# stm_board_f407_1_2_3.net
KiCad netlist of a schematic drawn in EAGLE
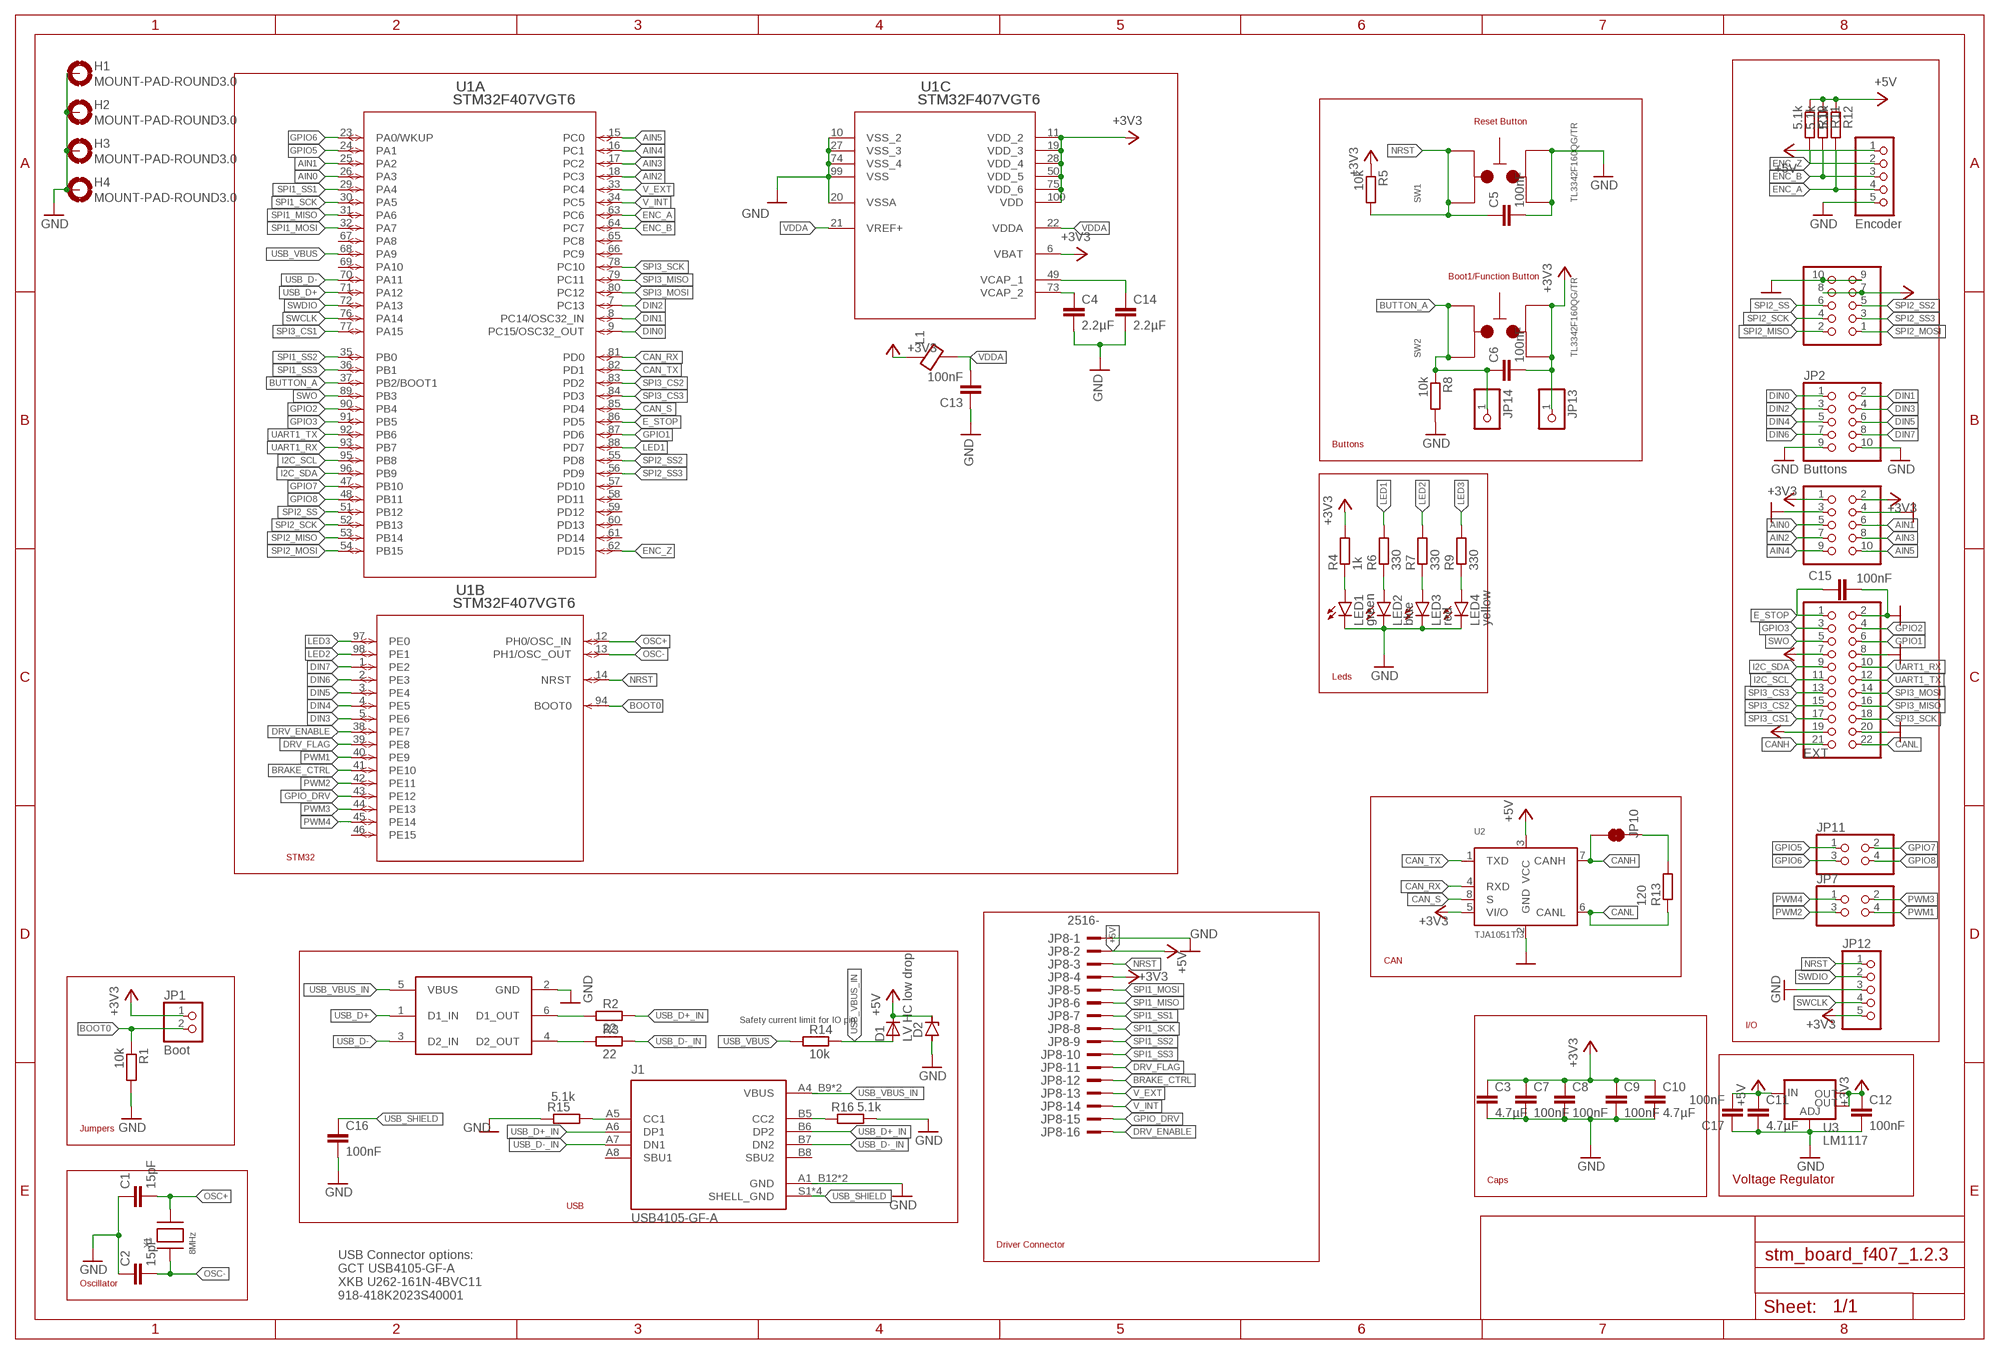
[diagram p0: schematic, sheet 1]

(export (version "E")
  (design (tool "Eeschema 10.0.6"))
  (components
    (comp (ref "C1")
      (value "15pF")
      (footprint "eagle-import:C0603")
      (libsource (lib "eagle-import") (part "C-EUC0603"))
    )
    (comp (ref "C2")
      (value "15pF")
      (footprint "eagle-import:C0603")
      (libsource (lib "eagle-import") (part "C-EUC0603"))
    )
    (comp (ref "C3")
      (value "4.7µF")
      (footprint "eagle-import:C0805")
      (libsource (lib "eagle-import") (part "C-EUC0805"))
    )
    (comp (ref "C4")
      (value "2.2µF")
      (footprint "eagle-import:C0603")
      (libsource (lib "eagle-import") (part "C-EUC0603"))
    )
    (comp (ref "C5")
      (value "100nF")
      (footprint "eagle-import:C0603")
      (libsource (lib "eagle-import") (part "C-EUC0603"))
    )
    (comp (ref "C6")
      (value "100nF")
      (footprint "eagle-import:C0603")
      (libsource (lib "eagle-import") (part "C-EUC0603"))
    )
    (comp (ref "C7")
      (value "100nF")
      (footprint "eagle-import:C0603")
      (libsource (lib "eagle-import") (part "C-EUC0603"))
    )
    (comp (ref "C8")
      (value "100nF")
      (footprint "eagle-import:C0603")
      (libsource (lib "eagle-import") (part "C-EUC0603"))
    )
    (comp (ref "C9")
      (value "100nF")
      (footprint "eagle-import:C0603")
      (libsource (lib "eagle-import") (part "C-EUC0603"))
    )
    (comp (ref "C10")
      (value "4.7µF")
      (footprint "eagle-import:C0805")
      (libsource (lib "eagle-import") (part "C-EUC0805"))
    )
    (comp (ref "C11")
      (value "4.7µF")
      (footprint "eagle-import:C0805")
      (libsource (lib "eagle-import") (part "C-EUC0805"))
    )
    (comp (ref "C12")
      (value "100nF")
      (footprint "eagle-import:C0603")
      (libsource (lib "eagle-import") (part "C-EUC0603"))
    )
    (comp (ref "C13")
      (value "100nF")
      (footprint "eagle-import:C0603")
      (libsource (lib "eagle-import") (part "C-EUC0603"))
    )
    (comp (ref "C14")
      (value "2.2µF")
      (footprint "eagle-import:C0603")
      (libsource (lib "eagle-import") (part "C-EUC0603"))
    )
    (comp (ref "C15")
      (value "100nF")
      (footprint "eagle-import:C0603")
      (libsource (lib "eagle-import") (part "C-EUC0603"))
    )
    (comp (ref "C16")
      (value "100nF")
      (footprint "eagle-import:C0603")
      (libsource (lib "eagle-import") (part "C-EUC0603"))
    )
    (comp (ref "C17")
      (value "100nF")
      (footprint "eagle-import:C0603")
      (libsource (lib "eagle-import") (part "C-EUC0603"))
    )
    (comp (ref "D1")
      (value "LV HC low drop")
      (footprint "eagle-import:SMADIODE")
      (libsource (lib "eagle-import") (part "DIODESMA"))
    )
    (comp (ref "D2")
      (value "ZENER-DIODESOD80C")
      (footprint "eagle-import:SOD80C")
      (libsource (lib "eagle-import") (part "ZENER-DIODESOD80C"))
    )
    (comp (ref "H1")
      (value "MOUNT-PAD-ROUND3.0")
      (footprint "eagle-import:3,0-PAD")
      (libsource (lib "eagle-import") (part "MOUNT-PAD-ROUND3.0"))
    )
    (comp (ref "H2")
      (value "MOUNT-PAD-ROUND3.0")
      (footprint "eagle-import:3,0-PAD")
      (libsource (lib "eagle-import") (part "MOUNT-PAD-ROUND3.0"))
    )
    (comp (ref "H3")
      (value "MOUNT-PAD-ROUND3.0")
      (footprint "eagle-import:3,0-PAD")
      (libsource (lib "eagle-import") (part "MOUNT-PAD-ROUND3.0"))
    )
    (comp (ref "H4")
      (value "MOUNT-PAD-ROUND3.0")
      (footprint "eagle-import:3,0-PAD")
      (libsource (lib "eagle-import") (part "MOUNT-PAD-ROUND3.0"))
    )
    (comp (ref "J1")
      (value "USB4105-GF-A")
      (footprint "eagle-import:GCT_USB4105-GF-A")
      (fields (field (name "MF") "GCT"))
      (libsource (lib "eagle-import") (part "USB4105-GF-A"))
    )
    (comp (ref "JP1")
      (value "Boot")
      (footprint "eagle-import:1X02")
      (libsource (lib "eagle-import") (part "PINHD-1X2"))
    )
    (comp (ref "JP2")
      (value "Buttons")
      (footprint "eagle-import:2X05")
      (libsource (lib "eagle-import") (part "PINHD-2X5"))
    )
    (comp (ref "JP3")
      (value "Analog")
      (footprint "eagle-import:2X05")
      (libsource (lib "eagle-import") (part "PINHD-2X5"))
    )
    (comp (ref "JP4")
      (value "EXT")
      (footprint "eagle-import:2X11")
      (libsource (lib "eagle-import") (part "PINHD-2X11"))
    )
    (comp (ref "JP5")
      (value "Encoder")
      (footprint "eagle-import:1X05")
      (libsource (lib "eagle-import") (part "PINHD-1X5"))
    )
    (comp (ref "JP6")
      (value "SPI")
      (footprint "eagle-import:2X05")
      (libsource (lib "eagle-import") (part "PINHD-2X5"))
    )
    (comp (ref "JP7")
      (value "PINHD-2X2")
      (footprint "eagle-import:2X02")
      (libsource (lib "eagle-import") (part "PINHD-2X2"))
    )
    (comp (ref "JP8")
      (value "2516-")
      (footprint "eagle-import:PAK100_2500-16")
      (libsource (lib "eagle-import") (part "2516-"))
    )
    (comp (ref "JP10")
      (value "JUMPER-SMT_2_NC_TRACE_SILK")
      (footprint "eagle-import:SMT-JUMPER_2_NC_TRACE_SILK")
      (libsource (lib "eagle-import") (part "JUMPER-SMT_2_NC_TRACE_SILK"))
    )
    (comp (ref "JP11")
      (value "PINHD-2X2")
      (footprint "eagle-import:2X02")
      (libsource (lib "eagle-import") (part "PINHD-2X2"))
    )
    (comp (ref "JP12")
      (value "PINHD-1X5")
      (footprint "eagle-import:1X05")
      (libsource (lib "eagle-import") (part "PINHD-1X5"))
    )
    (comp (ref "JP13")
      (value "PINHD-1X1")
      (footprint "eagle-import:1X01")
      (libsource (lib "eagle-import") (part "PINHD-1X1"))
    )
    (comp (ref "JP14")
      (value "PINHD-1X1")
      (footprint "eagle-import:1X01")
      (libsource (lib "eagle-import") (part "PINHD-1X1"))
    )
    (comp (ref "L1")
      (value "GZ2012D601TF")
      (footprint "eagle-import:BLM21PG331SN1D")
      (fields
        (field (name "DIGIKEY_PART_NUMBER") "490-5988-2-ND")
        (field (name "MANUFACTURER") "Murata Electronics North America")
        (field (name "MPN") "BLM21PG331SN1D")
        (field (name "CREATED_BY") "PCBLayout.com")
      )
      (libsource (lib "eagle-import") (part "BLM21PG331SN1D"))
    )
    (comp (ref "LED1")
      (value "green")
      (footprint "eagle-import:SML0805")
      (libsource (lib "eagle-import") (part "LEDSML0805"))
    )
    (comp (ref "LED2")
      (value "blue")
      (footprint "eagle-import:SML0805")
      (libsource (lib "eagle-import") (part "LEDSML0805"))
    )
    (comp (ref "LED3")
      (value "red")
      (footprint "eagle-import:SML0805")
      (libsource (lib "eagle-import") (part "LEDSML0805"))
    )
    (comp (ref "LED4")
      (value "yellow")
      (footprint "eagle-import:SML0805")
      (libsource (lib "eagle-import") (part "LEDSML0805"))
    )
    (comp (ref "R1")
      (value "10k")
      (footprint "eagle-import:R0603")
      (libsource (lib "eagle-import") (part "R-EU_R0603"))
    )
    (comp (ref "R2")
      (value "22")
      (footprint "eagle-import:R0603")
      (libsource (lib "eagle-import") (part "R-EU_R0603"))
    )
    (comp (ref "R3")
      (value "22")
      (footprint "eagle-import:R0603")
      (libsource (lib "eagle-import") (part "R-EU_R0603"))
    )
    (comp (ref "R4")
      (value "1k")
      (footprint "eagle-import:R0603")
      (libsource (lib "eagle-import") (part "R-EU_R0603"))
    )
    (comp (ref "R5")
      (value "10k")
      (footprint "eagle-import:R0603")
      (libsource (lib "eagle-import") (part "R-EU_R0603"))
    )
    (comp (ref "R6")
      (value "330")
      (footprint "eagle-import:R0603")
      (libsource (lib "eagle-import") (part "R-EU_R0603"))
    )
    (comp (ref "R7")
      (value "330")
      (footprint "eagle-import:R0603")
      (libsource (lib "eagle-import") (part "R-EU_R0603"))
    )
    (comp (ref "R8")
      (value "10k")
      (footprint "eagle-import:R0603")
      (libsource (lib "eagle-import") (part "R-EU_R0603"))
    )
    (comp (ref "R9")
      (value "330")
      (footprint "eagle-import:R0603")
      (libsource (lib "eagle-import") (part "R-EU_R0603"))
    )
    (comp (ref "R10")
      (value "5.1k")
      (footprint "eagle-import:R0603")
      (libsource (lib "eagle-import") (part "R-EU_R0603"))
    )
    (comp (ref "R11")
      (value "5.1k")
      (footprint "eagle-import:R0603")
      (libsource (lib "eagle-import") (part "R-EU_R0603"))
    )
    (comp (ref "R12")
      (value "5.1k")
      (footprint "eagle-import:R0603")
      (libsource (lib "eagle-import") (part "R-EU_R0603"))
    )
    (comp (ref "R13")
      (value "120")
      (footprint "eagle-import:R0603")
      (libsource (lib "eagle-import") (part "R-EU_R0603"))
    )
    (comp (ref "R14")
      (value "10k")
      (footprint "eagle-import:R0603")
      (libsource (lib "eagle-import") (part "R-EU_R0603"))
    )
    (comp (ref "R15")
      (value "5.1k")
      (footprint "eagle-import:R0603")
      (libsource (lib "eagle-import") (part "R-EU_R0603"))
    )
    (comp (ref "R16")
      (value "5.1k")
      (footprint "eagle-import:R0603")
      (libsource (lib "eagle-import") (part "R-EU_R0603"))
    )
    (comp (ref "SW1")
      (value "TL3342F160QG/TR")
      (footprint "eagle-import:TL3342F160QG_TR")
      (fields
        (field (name "DIGI_KEY_PART_NUMBER") "EG2531CT-ND")
        (field (name "MANUFACTURER") "E-Switch")
        (field (name "CREATED_BY") "PCBLayout.com")
      )
      (libsource (lib "eagle-import") (part "TL3342F160QG/TR"))
    )
    (comp (ref "SW2")
      (value "TL3342F160QG/TR")
      (footprint "eagle-import:TL3342F160QG_TR")
      (fields
        (field (name "DIGI_KEY_PART_NUMBER") "EG2531CT-ND")
        (field (name "MANUFACTURER") "E-Switch")
        (field (name "CREATED_BY") "PCBLayout.com")
      )
      (libsource (lib "eagle-import") (part "TL3342F160QG/TR"))
    )
    (comp (ref "U1")
      (value "STM32F407VGT6")
      (footprint "eagle-import:LQFP100-14X14MM")
      (fields (field (name "COPYRIGHT") "Copyright (C) 2018 Accelerated Designs. All rights reserved"))
      (libsource (lib "eagle-import") (part "STM32F407VGT6"))
    )
    (comp (ref "U2")
      (value "TJA1051T/3")
      (footprint "eagle-import:SOT96-1")
      (fields (field (name "MF") "NXP Semiconductors"))
      (libsource (lib "eagle-import") (part "TJA1051T/3"))
    )
    (comp (ref "U3")
      (value "LM1117")
      (footprint "eagle-import:SOT223")
      (libsource (lib "eagle-import") (part "V_REG_LM1117SOT223"))
    )
    (comp (ref "U4")
      (value "USBLC6-2SC6")
      (footprint "eagle-import:TSOT-23-6")
      (libsource (lib "eagle-import") (part "USBLC6-2SC6"))
    )
    (comp (ref "X1")
      (value "8MHz")
      (footprint "eagle-import:NX5032")
      (libsource (lib "eagle-import") (part "XTALNX5032"))
    )
  )
  (nets
    (net (code "1") (name "+3V3") (class "Default")
      (node (ref "C10") (pin "1") (pinfunction "1_1") (pintype "passive"))
      (node (ref "C12") (pin "1") (pinfunction "1_1") (pintype "passive"))
      (node (ref "C3") (pin "1") (pinfunction "1_1") (pintype "passive"))
      (node (ref "C6") (pin "2") (pinfunction "2_2") (pintype "passive"))
      (node (ref "C7") (pin "1") (pinfunction "1_1") (pintype "passive"))
      (node (ref "C8") (pin "1") (pinfunction "1_1") (pintype "passive"))
      (node (ref "C9") (pin "1") (pinfunction "1_1") (pintype "passive"))
      (node (ref "JP1") (pin "1") (pinfunction "1_1") (pintype "passive"))
      (node (ref "JP12") (pin "5") (pinfunction "5_5") (pintype "passive"))
      (node (ref "JP13") (pin "1") (pinfunction "1_1") (pintype "passive"))
      (node (ref "JP3") (pin "1") (pinfunction "1_1") (pintype "passive"))
      (node (ref "JP3") (pin "2") (pinfunction "2_2") (pintype "passive"))
      (node (ref "JP4") (pin "7") (pinfunction "7_7") (pintype "passive"))
      (node (ref "JP6") (pin "7") (pinfunction "7_7") (pintype "passive"))
      (node (ref "JP6") (pin "8") (pinfunction "8_8") (pintype "passive"))
      (node (ref "JP8") (pin "4") (pinfunction "KL_4") (pintype "passive"))
      (node (ref "L1") (pin "1") (pinfunction "1_1") (pintype "passive"))
      (node (ref "R4") (pin "2") (pinfunction "2_2") (pintype "passive"))
      (node (ref "R5") (pin "1") (pinfunction "1_1") (pintype "passive"))
      (node (ref "SW2") (pin "1") (pinfunction "1_1") (pintype "passive"))
      (node (ref "SW2") (pin "2") (pinfunction "2_2") (pintype "passive"))
      (node (ref "U1") (pin "100") (pinfunction "VDD_100") (pintype "power_in"))
      (node (ref "U1") (pin "11") (pinfunction "VDD_2_11") (pintype "power_in"))
      (node (ref "U1") (pin "19") (pinfunction "VDD_3_19") (pintype "power_in"))
      (node (ref "U1") (pin "28") (pinfunction "VDD_4_28") (pintype "power_in"))
      (node (ref "U1") (pin "50") (pinfunction "VDD_5_50") (pintype "power_in"))
      (node (ref "U1") (pin "6") (pinfunction "VBAT_6") (pintype "power_in"))
      (node (ref "U1") (pin "75") (pinfunction "VDD_6_75") (pintype "power_in"))
      (node (ref "U2") (pin "5") (pinfunction "VI/O_5") (pintype "passive"))
      (node (ref "U3") (pin "2") (pinfunction "OUT_2") (pintype "output"))
      (node (ref "U3") (pin "4") (pinfunction "OUT_4") (pintype "output"))
    )
    (net (code "2") (name "+5V") (class "Default")
      (node (ref "C11") (pin "1") (pinfunction "1_1") (pintype "passive"))
      (node (ref "C17") (pin "2") (pinfunction "2_2") (pintype "passive"))
      (node (ref "D1") (pin "C") (pinfunction "C_C") (pintype "passive"))
      (node (ref "D2") (pin "C") (pinfunction "C_C") (pintype "passive"))
      (node (ref "JP4") (pin "19") (pinfunction "19_19") (pintype "passive"))
      (node (ref "JP5") (pin "1") (pinfunction "1_1") (pintype "passive"))
      (node (ref "JP8") (pin "2") (pinfunction "KL_2") (pintype "passive"))
      (node (ref "R10") (pin "1") (pinfunction "1_1") (pintype "passive"))
      (node (ref "R11") (pin "1") (pinfunction "1_1") (pintype "passive"))
      (node (ref "R12") (pin "1") (pinfunction "1_1") (pintype "passive"))
      (node (ref "U2") (pin "3") (pinfunction "VCC_3") (pintype "bidirectional"))
      (node (ref "U3") (pin "3") (pinfunction "IN_3") (pintype "input"))
    )
    (net (code "3") (name "AIN0") (class "Default")
      (node (ref "JP3") (pin "5") (pinfunction "5_5") (pintype "passive"))
      (node (ref "U1") (pin "26") (pinfunction "PA3_26") (pintype "bidirectional"))
    )
    (net (code "4") (name "AIN1") (class "Default")
      (node (ref "JP3") (pin "6") (pinfunction "6_6") (pintype "passive"))
      (node (ref "U1") (pin "25") (pinfunction "PA2_25") (pintype "bidirectional"))
    )
    (net (code "5") (name "AIN2") (class "Default")
      (node (ref "JP3") (pin "7") (pinfunction "7_7") (pintype "passive"))
      (node (ref "U1") (pin "18") (pinfunction "PC3_18") (pintype "bidirectional"))
    )
    (net (code "6") (name "AIN3") (class "Default")
      (node (ref "JP3") (pin "8") (pinfunction "8_8") (pintype "passive"))
      (node (ref "U1") (pin "17") (pinfunction "PC2_17") (pintype "bidirectional"))
    )
    (net (code "7") (name "AIN4") (class "Default")
      (node (ref "JP3") (pin "9") (pinfunction "9_9") (pintype "passive"))
      (node (ref "U1") (pin "16") (pinfunction "PC1_16") (pintype "bidirectional"))
    )
    (net (code "8") (name "AIN5") (class "Default")
      (node (ref "JP3") (pin "10") (pinfunction "10_10") (pintype "passive"))
      (node (ref "U1") (pin "15") (pinfunction "PC0_15") (pintype "bidirectional"))
    )
    (net (code "9") (name "BOOT0") (class "Default")
      (node (ref "JP1") (pin "2") (pinfunction "2_2") (pintype "passive"))
      (node (ref "R1") (pin "1") (pinfunction "1_1") (pintype "passive"))
      (node (ref "U1") (pin "94") (pinfunction "BOOT0_94") (pintype "input"))
    )
    (net (code "10") (name "BRAKE_CTRL") (class "Default")
      (node (ref "JP8") (pin "12") (pinfunction "KL_12") (pintype "passive"))
      (node (ref "U1") (pin "41") (pinfunction "PE10_41") (pintype "bidirectional"))
    )
    (net (code "11") (name "BUTTON_A") (class "Default")
      (node (ref "C6") (pin "1") (pinfunction "1_1") (pintype "passive"))
      (node (ref "JP14") (pin "1") (pinfunction "1_1") (pintype "passive"))
      (node (ref "R8") (pin "1") (pinfunction "1_1") (pintype "passive"))
      (node (ref "SW2") (pin "3") (pinfunction "3_3") (pintype "passive"))
      (node (ref "SW2") (pin "4") (pinfunction "4_4") (pintype "passive"))
      (node (ref "U1") (pin "37") (pinfunction "PB2/BOOT1_37") (pintype "bidirectional"))
    )
    (net (code "12") (name "CANH") (class "Default")
      (node (ref "JP10") (pin "2") (pinfunction "2_2") (pintype "passive"))
      (node (ref "JP4") (pin "21") (pinfunction "21_21") (pintype "passive"))
      (node (ref "U2") (pin "7") (pinfunction "CANH_7") (pintype "bidirectional"))
    )
    (net (code "13") (name "CANL") (class "Default")
      (node (ref "JP4") (pin "22") (pinfunction "22_22") (pintype "passive"))
      (node (ref "R13") (pin "1") (pinfunction "1_1") (pintype "passive"))
      (node (ref "U2") (pin "6") (pinfunction "CANL_6") (pintype "bidirectional"))
    )
    (net (code "14") (name "CAN_RX") (class "Default")
      (node (ref "U1") (pin "81") (pinfunction "PD0_81") (pintype "bidirectional"))
      (node (ref "U2") (pin "4") (pinfunction "RXD_4") (pintype "bidirectional"))
    )
    (net (code "15") (name "CAN_S") (class "Default")
      (node (ref "U1") (pin "85") (pinfunction "PD4_85") (pintype "bidirectional"))
      (node (ref "U2") (pin "8") (pinfunction "S_8") (pintype "power_in"))
    )
    (net (code "16") (name "CAN_TX") (class "Default")
      (node (ref "U1") (pin "82") (pinfunction "PD1_82") (pintype "bidirectional"))
      (node (ref "U2") (pin "1") (pinfunction "TXD_1") (pintype "output"))
    )
    (net (code "17") (name "DIN0") (class "Default")
      (node (ref "JP2") (pin "1") (pinfunction "1_1") (pintype "passive"))
      (node (ref "U1") (pin "9") (pinfunction "PC15/OSC32_OUT_9") (pintype "bidirectional"))
    )
    (net (code "18") (name "DIN1") (class "Default")
      (node (ref "JP2") (pin "2") (pinfunction "2_2") (pintype "passive"))
      (node (ref "U1") (pin "8") (pinfunction "PC14/OSC32_IN_8") (pintype "bidirectional"))
    )
    (net (code "19") (name "DIN2") (class "Default")
      (node (ref "JP2") (pin "3") (pinfunction "3_3") (pintype "passive"))
      (node (ref "U1") (pin "7") (pinfunction "PC13_7") (pintype "bidirectional"))
    )
    (net (code "20") (name "DIN3") (class "Default")
      (node (ref "JP2") (pin "4") (pinfunction "4_4") (pintype "passive"))
      (node (ref "U1") (pin "5") (pinfunction "PE6_5") (pintype "bidirectional"))
    )
    (net (code "21") (name "DIN4") (class "Default")
      (node (ref "JP2") (pin "5") (pinfunction "5_5") (pintype "passive"))
      (node (ref "U1") (pin "4") (pinfunction "PE5_4") (pintype "bidirectional"))
    )
    (net (code "22") (name "DIN5") (class "Default")
      (node (ref "JP2") (pin "6") (pinfunction "6_6") (pintype "passive"))
      (node (ref "U1") (pin "3") (pinfunction "PE4_3") (pintype "bidirectional"))
    )
    (net (code "23") (name "DIN6") (class "Default")
      (node (ref "JP2") (pin "7") (pinfunction "7_7") (pintype "passive"))
      (node (ref "U1") (pin "2") (pinfunction "PE3_2") (pintype "bidirectional"))
    )
    (net (code "24") (name "DIN7") (class "Default")
      (node (ref "JP2") (pin "8") (pinfunction "8_8") (pintype "passive"))
      (node (ref "U1") (pin "1") (pinfunction "PE2_1") (pintype "bidirectional"))
    )
    (net (code "25") (name "DRV_ENABLE") (class "Default")
      (node (ref "JP8") (pin "16") (pinfunction "KL_16") (pintype "passive"))
      (node (ref "U1") (pin "38") (pinfunction "PE7_38") (pintype "bidirectional"))
    )
    (net (code "26") (name "DRV_FLAG") (class "Default")
      (node (ref "JP8") (pin "11") (pinfunction "KL_11") (pintype "passive"))
      (node (ref "U1") (pin "39") (pinfunction "PE8_39") (pintype "bidirectional"))
    )
    (net (code "27") (name "ENC_A") (class "Default")
      (node (ref "JP5") (pin "4") (pinfunction "4_4") (pintype "passive"))
      (node (ref "R12") (pin "2") (pinfunction "2_2") (pintype "passive"))
      (node (ref "U1") (pin "63") (pinfunction "PC6_63") (pintype "bidirectional"))
    )
    (net (code "28") (name "ENC_B") (class "Default")
      (node (ref "JP5") (pin "3") (pinfunction "3_3") (pintype "passive"))
      (node (ref "R11") (pin "2") (pinfunction "2_2") (pintype "passive"))
      (node (ref "U1") (pin "64") (pinfunction "PC7_64") (pintype "bidirectional"))
    )
    (net (code "29") (name "ENC_Z") (class "Default")
      (node (ref "JP5") (pin "2") (pinfunction "2_2") (pintype "passive"))
      (node (ref "R10") (pin "2") (pinfunction "2_2") (pintype "passive"))
      (node (ref "U1") (pin "62") (pinfunction "PD15_62") (pintype "bidirectional"))
    )
    (net (code "30") (name "E_STOP") (class "Default")
      (node (ref "C15") (pin "1") (pinfunction "1_1") (pintype "passive"))
      (node (ref "JP4") (pin "1") (pinfunction "1_1") (pintype "passive"))
      (node (ref "U1") (pin "86") (pinfunction "PD5_86") (pintype "bidirectional"))
    )
    (net (code "31") (name "GND") (class "Default")
      (node (ref "C1") (pin "1") (pinfunction "1_1") (pintype "passive"))
      (node (ref "C10") (pin "2") (pinfunction "2_2") (pintype "passive"))
      (node (ref "C11") (pin "2") (pinfunction "2_2") (pintype "passive"))
      (node (ref "C12") (pin "2") (pinfunction "2_2") (pintype "passive"))
      (node (ref "C13") (pin "1") (pinfunction "1_1") (pintype "passive"))
      (node (ref "C14") (pin "2") (pinfunction "2_2") (pintype "passive"))
      (node (ref "C15") (pin "2") (pinfunction "2_2") (pintype "passive"))
      (node (ref "C16") (pin "2") (pinfunction "2_2") (pintype "passive"))
      (node (ref "C17") (pin "1") (pinfunction "1_1") (pintype "passive"))
      (node (ref "C2") (pin "1") (pinfunction "1_1") (pintype "passive"))
      (node (ref "C3") (pin "2") (pinfunction "2_2") (pintype "passive"))
      (node (ref "C4") (pin "2") (pinfunction "2_2") (pintype "passive"))
      (node (ref "C5") (pin "2") (pinfunction "2_2") (pintype "passive"))
      (node (ref "C7") (pin "2") (pinfunction "2_2") (pintype "passive"))
      (node (ref "C8") (pin "2") (pinfunction "2_2") (pintype "passive"))
      (node (ref "C9") (pin "2") (pinfunction "2_2") (pintype "passive"))
      (node (ref "D2") (pin "A") (pinfunction "A_A") (pintype "passive"))
      (node (ref "H1") (pin "B3,0") (pinfunction "MOUNT_B3,0") (pintype "passive"))
      (node (ref "H2") (pin "B3,0") (pinfunction "MOUNT_B3,0") (pintype "passive"))
      (node (ref "H3") (pin "B3,0") (pinfunction "MOUNT_B3,0") (pintype "passive"))
      (node (ref "H4") (pin "B3,0") (pinfunction "MOUNT_B3,0") (pintype "passive"))
      (node (ref "J1") (pin "A1_B12") (pinfunction "GND_A1_B12") (pintype "power_in"))
      (node (ref "J1") (pin "B1_A12") (pinfunction "GND_B1_A12") (pintype "power_in"))
      (node (ref "JP12") (pin "3") (pinfunction "3_3") (pintype "passive"))
      (node (ref "JP2") (pin "10") (pinfunction "10_10") (pintype "passive"))
      (node (ref "JP2") (pin "9") (pinfunction "9_9") (pintype "passive"))
      (node (ref "JP3") (pin "3") (pinfunction "3_3") (pintype "passive"))
      (node (ref "JP3") (pin "4") (pinfunction "4_4") (pintype "passive"))
      (node (ref "JP4") (pin "2") (pinfunction "2_2") (pintype "passive"))
      (node (ref "JP4") (pin "20") (pinfunction "20_20") (pintype "passive"))
      (node (ref "JP4") (pin "8") (pinfunction "8_8") (pintype "passive"))
      (node (ref "JP5") (pin "5") (pinfunction "5_5") (pintype "passive"))
      (node (ref "JP6") (pin "10") (pinfunction "10_10") (pintype "passive"))
      (node (ref "JP6") (pin "9") (pinfunction "9_9") (pintype "passive"))
      (node (ref "JP8") (pin "1") (pinfunction "KL_1") (pintype "passive"))
      (node (ref "LED1") (pin "C") (pinfunction "C_C") (pintype "passive"))
      (node (ref "LED2") (pin "C") (pinfunction "C_C") (pintype "passive"))
      (node (ref "LED3") (pin "C") (pinfunction "C_C") (pintype "passive"))
      (node (ref "LED4") (pin "C") (pinfunction "C_C") (pintype "passive"))
      (node (ref "R1") (pin "2") (pinfunction "2_2") (pintype "passive"))
      (node (ref "R15") (pin "1") (pinfunction "1_1") (pintype "passive"))
      (node (ref "R16") (pin "2") (pinfunction "2_2") (pintype "passive"))
      (node (ref "R8") (pin "2") (pinfunction "2_2") (pintype "passive"))
      (node (ref "SW1") (pin "1") (pinfunction "1_1") (pintype "passive"))
      (node (ref "SW1") (pin "2") (pinfunction "2_2") (pintype "passive"))
      (node (ref "U1") (pin "10") (pinfunction "VSS_2_10") (pintype "power_in"))
      (node (ref "U1") (pin "20") (pinfunction "VSSA_20") (pintype "power_in"))
      (node (ref "U1") (pin "27") (pinfunction "VSS_3_27") (pintype "power_in"))
      (node (ref "U1") (pin "74") (pinfunction "VSS_4_74") (pintype "power_in"))
      (node (ref "U1") (pin "99") (pinfunction "VSS_99") (pintype "power_in"))
      (node (ref "U2") (pin "2") (pinfunction "GND_2") (pintype "bidirectional"))
      (node (ref "U3") (pin "1") (pinfunction "ADJ_1") (pintype "input"))
      (node (ref "U4") (pin "2") (pinfunction "GND_2") (pintype "bidirectional"))
    )
    (net (code "32") (name "GPIO1") (class "Default")
      (node (ref "JP4") (pin "6") (pinfunction "6_6") (pintype "passive"))
      (node (ref "U1") (pin "87") (pinfunction "PD6_87") (pintype "bidirectional"))
    )
    (net (code "33") (name "GPIO2") (class "Default")
      (node (ref "JP4") (pin "4") (pinfunction "4_4") (pintype "passive"))
      (node (ref "U1") (pin "90") (pinfunction "PB4_90") (pintype "bidirectional"))
    )
    (net (code "34") (name "GPIO3") (class "Default")
      (node (ref "JP4") (pin "3") (pinfunction "3_3") (pintype "passive"))
      (node (ref "U1") (pin "91") (pinfunction "PB5_91") (pintype "bidirectional"))
    )
    (net (code "35") (name "GPIO5") (class "Default")
      (node (ref "JP11") (pin "1") (pinfunction "1_1") (pintype "passive"))
      (node (ref "U1") (pin "24") (pinfunction "PA1_24") (pintype "bidirectional"))
    )
    (net (code "36") (name "GPIO6") (class "Default")
      (node (ref "JP11") (pin "3") (pinfunction "3_3") (pintype "passive"))
      (node (ref "U1") (pin "23") (pinfunction "PA0/WKUP_23") (pintype "bidirectional"))
    )
    (net (code "37") (name "GPIO7") (class "Default")
      (node (ref "JP11") (pin "2") (pinfunction "2_2") (pintype "passive"))
      (node (ref "U1") (pin "47") (pinfunction "PB10_47") (pintype "bidirectional"))
    )
    (net (code "38") (name "GPIO8") (class "Default")
      (node (ref "JP11") (pin "4") (pinfunction "4_4") (pintype "passive"))
      (node (ref "U1") (pin "48") (pinfunction "PB11_48") (pintype "bidirectional"))
    )
    (net (code "39") (name "GPIO_DRV") (class "Default")
      (node (ref "JP8") (pin "15") (pinfunction "KL_15") (pintype "passive"))
      (node (ref "U1") (pin "43") (pinfunction "PE12_43") (pintype "bidirectional"))
    )
    (net (code "40") (name "I2C_SCL") (class "Default")
      (node (ref "JP4") (pin "11") (pinfunction "11_11") (pintype "passive"))
      (node (ref "U1") (pin "95") (pinfunction "PB8_95") (pintype "bidirectional"))
    )
    (net (code "41") (name "I2C_SDA") (class "Default")
      (node (ref "JP4") (pin "9") (pinfunction "9_9") (pintype "passive"))
      (node (ref "U1") (pin "96") (pinfunction "PB9_96") (pintype "bidirectional"))
    )
    (net (code "42") (name "LED1") (class "Default")
      (node (ref "R6") (pin "2") (pinfunction "2_2") (pintype "passive"))
      (node (ref "U1") (pin "88") (pinfunction "PD7_88") (pintype "bidirectional"))
    )
    (net (code "43") (name "LED2") (class "Default")
      (node (ref "R7") (pin "2") (pinfunction "2_2") (pintype "passive"))
      (node (ref "U1") (pin "98") (pinfunction "PE1_98") (pintype "bidirectional"))
    )
    (net (code "44") (name "LED3") (class "Default")
      (node (ref "R9") (pin "2") (pinfunction "2_2") (pintype "passive"))
      (node (ref "U1") (pin "97") (pinfunction "PE0_97") (pintype "bidirectional"))
    )
    (net (code "45") (name "NRST") (class "Default")
      (node (ref "C5") (pin "1") (pinfunction "1_1") (pintype "passive"))
      (node (ref "JP12") (pin "1") (pinfunction "1_1") (pintype "passive"))
      (node (ref "JP8") (pin "3") (pinfunction "KL_3") (pintype "passive"))
      (node (ref "R5") (pin "2") (pinfunction "2_2") (pintype "passive"))
      (node (ref "SW1") (pin "3") (pinfunction "3_3") (pintype "passive"))
      (node (ref "SW1") (pin "4") (pinfunction "4_4") (pintype "passive"))
      (node (ref "U1") (pin "14") (pinfunction "NRST_14") (pintype "bidirectional"))
    )
    (net (code "46") (name "Net-(J1-CC1)") (class "Default")
      (node (ref "J1") (pin "A5") (pinfunction "CC1_A5") (pintype "bidirectional"))
      (node (ref "R15") (pin "2") (pinfunction "2_2") (pintype "passive"))
    )
    (net (code "47") (name "Net-(J1-CC2)") (class "Default")
      (node (ref "J1") (pin "B5") (pinfunction "CC2_B5") (pintype "bidirectional"))
      (node (ref "R16") (pin "1") (pinfunction "1_1") (pintype "passive"))
    )
    (net (code "48") (name "Net-(JP10-Pad1)") (class "Default")
      (node (ref "JP10") (pin "1") (pinfunction "1_1") (pintype "passive"))
      (node (ref "R13") (pin "2") (pinfunction "2_2") (pintype "passive"))
    )
    (net (code "49") (name "Net-(LED1-PadA)") (class "Default")
      (node (ref "LED1") (pin "A") (pinfunction "A_A") (pintype "passive"))
      (node (ref "R4") (pin "1") (pinfunction "1_1") (pintype "passive"))
    )
    (net (code "50") (name "Net-(LED2-PadA)") (class "Default")
      (node (ref "LED2") (pin "A") (pinfunction "A_A") (pintype "passive"))
      (node (ref "R6") (pin "1") (pinfunction "1_1") (pintype "passive"))
    )
    (net (code "51") (name "Net-(LED3-PadA)") (class "Default")
      (node (ref "LED3") (pin "A") (pinfunction "A_A") (pintype "passive"))
      (node (ref "R7") (pin "1") (pinfunction "1_1") (pintype "passive"))
    )
    (net (code "52") (name "Net-(LED4-PadA)") (class "Default")
      (node (ref "LED4") (pin "A") (pinfunction "A_A") (pintype "passive"))
      (node (ref "R9") (pin "1") (pinfunction "1_1") (pintype "passive"))
    )
    (net (code "53") (name "Net-(U1C-VCAP_1)") (class "Default")
      (node (ref "C14") (pin "1") (pinfunction "1_1") (pintype "passive"))
      (node (ref "U1") (pin "49") (pinfunction "VCAP_1_49") (pintype "power_in"))
    )
    (net (code "54") (name "Net-(U1C-VCAP_2)") (class "Default")
      (node (ref "C4") (pin "1") (pinfunction "1_1") (pintype "passive"))
      (node (ref "U1") (pin "73") (pinfunction "VCAP_2_73") (pintype "power_in"))
    )
    (net (code "55") (name "Net-(U4-D1_OUT)") (class "Default")
      (node (ref "R2") (pin "1") (pinfunction "1_1") (pintype "passive"))
      (node (ref "U4") (pin "6") (pinfunction "D1_OUT_6") (pintype "bidirectional"))
    )
    (net (code "56") (name "Net-(U4-D2_OUT)") (class "Default")
      (node (ref "R3") (pin "1") (pinfunction "1_1") (pintype "passive"))
      (node (ref "U4") (pin "4") (pinfunction "D2_OUT_4") (pintype "bidirectional"))
    )
    (net (code "57") (name "OSC+") (class "Default")
      (node (ref "C1") (pin "2") (pinfunction "2_2") (pintype "passive"))
      (node (ref "U1") (pin "12") (pinfunction "PH0/OSC_IN_12") (pintype "bidirectional"))
      (node (ref "X1") (pin "P$2") (pinfunction "P$2_P$2") (pintype "bidirectional"))
    )
    (net (code "58") (name "OSC-") (class "Default")
      (node (ref "C2") (pin "2") (pinfunction "2_2") (pintype "passive"))
      (node (ref "U1") (pin "13") (pinfunction "PH1/OSC_OUT_13") (pintype "bidirectional"))
      (node (ref "X1") (pin "P$1") (pinfunction "P$1_P$1") (pintype "bidirectional"))
    )
    (net (code "59") (name "PWM1") (class "Default")
      (node (ref "JP7") (pin "4") (pinfunction "4_4") (pintype "passive"))
      (node (ref "U1") (pin "40") (pinfunction "PE9_40") (pintype "bidirectional"))
    )
    (net (code "60") (name "PWM2") (class "Default")
      (node (ref "JP7") (pin "3") (pinfunction "3_3") (pintype "passive"))
      (node (ref "U1") (pin "42") (pinfunction "PE11_42") (pintype "bidirectional"))
    )
    (net (code "61") (name "PWM3") (class "Default")
      (node (ref "JP7") (pin "2") (pinfunction "2_2") (pintype "passive"))
      (node (ref "U1") (pin "44") (pinfunction "PE13_44") (pintype "bidirectional"))
    )
    (net (code "62") (name "PWM4") (class "Default")
      (node (ref "JP7") (pin "1") (pinfunction "1_1") (pintype "passive"))
      (node (ref "U1") (pin "45") (pinfunction "PE14_45") (pintype "bidirectional"))
    )
    (net (code "63") (name "SPI1_MISO") (class "Default")
      (node (ref "JP8") (pin "6") (pinfunction "KL_6") (pintype "passive"))
      (node (ref "U1") (pin "31") (pinfunction "PA6_31") (pintype "bidirectional"))
    )
    (net (code "64") (name "SPI1_MOSI") (class "Default")
      (node (ref "JP8") (pin "5") (pinfunction "KL_5") (pintype "passive"))
      (node (ref "U1") (pin "32") (pinfunction "PA7_32") (pintype "bidirectional"))
    )
    (net (code "65") (name "SPI1_SCK") (class "Default")
      (node (ref "JP8") (pin "8") (pinfunction "KL_8") (pintype "passive"))
      (node (ref "U1") (pin "30") (pinfunction "PA5_30") (pintype "bidirectional"))
    )
    (net (code "66") (name "SPI1_SS1") (class "Default")
      (node (ref "JP8") (pin "7") (pinfunction "KL_7") (pintype "passive"))
      (node (ref "U1") (pin "29") (pinfunction "PA4_29") (pintype "bidirectional"))
    )
    (net (code "67") (name "SPI1_SS2") (class "Default")
      (node (ref "JP8") (pin "9") (pinfunction "KL_9") (pintype "passive"))
      (node (ref "U1") (pin "35") (pinfunction "PB0_35") (pintype "bidirectional"))
    )
    (net (code "68") (name "SPI1_SS3") (class "Default")
      (node (ref "JP8") (pin "10") (pinfunction "KL_10") (pintype "passive"))
      (node (ref "U1") (pin "36") (pinfunction "PB1_36") (pintype "bidirectional"))
    )
    (net (code "69") (name "SPI2_MISO") (class "Default")
      (node (ref "JP6") (pin "2") (pinfunction "2_2") (pintype "passive"))
      (node (ref "U1") (pin "53") (pinfunction "PB14_53") (pintype "bidirectional"))
    )
    (net (code "70") (name "SPI2_MOSI") (class "Default")
      (node (ref "JP6") (pin "1") (pinfunction "1_1") (pintype "passive"))
      (node (ref "U1") (pin "54") (pinfunction "PB15_54") (pintype "bidirectional"))
    )
    (net (code "71") (name "SPI2_SCK") (class "Default")
      (node (ref "JP6") (pin "4") (pinfunction "4_4") (pintype "passive"))
      (node (ref "U1") (pin "52") (pinfunction "PB13_52") (pintype "bidirectional"))
    )
    (net (code "72") (name "SPI2_SS") (class "Default")
      (node (ref "JP6") (pin "6") (pinfunction "6_6") (pintype "passive"))
      (node (ref "U1") (pin "51") (pinfunction "PB12_51") (pintype "bidirectional"))
    )
    (net (code "73") (name "SPI2_SS2") (class "Default")
      (node (ref "JP6") (pin "5") (pinfunction "5_5") (pintype "passive"))
      (node (ref "U1") (pin "55") (pinfunction "PD8_55") (pintype "bidirectional"))
    )
    (net (code "74") (name "SPI2_SS3") (class "Default")
      (node (ref "JP6") (pin "3") (pinfunction "3_3") (pintype "passive"))
      (node (ref "U1") (pin "56") (pinfunction "PD9_56") (pintype "bidirectional"))
    )
    (net (code "75") (name "SPI3_CS1") (class "Default")
      (node (ref "JP4") (pin "17") (pinfunction "17_17") (pintype "passive"))
      (node (ref "U1") (pin "77") (pinfunction "PA15_77") (pintype "bidirectional"))
    )
    (net (code "76") (name "SPI3_CS2") (class "Default")
      (node (ref "JP4") (pin "15") (pinfunction "15_15") (pintype "passive"))
      (node (ref "U1") (pin "83") (pinfunction "PD2_83") (pintype "bidirectional"))
    )
    (net (code "77") (name "SPI3_CS3") (class "Default")
      (node (ref "JP4") (pin "13") (pinfunction "13_13") (pintype "passive"))
      (node (ref "U1") (pin "84") (pinfunction "PD3_84") (pintype "bidirectional"))
    )
    (net (code "78") (name "SPI3_MISO") (class "Default")
      (node (ref "JP4") (pin "16") (pinfunction "16_16") (pintype "passive"))
      (node (ref "U1") (pin "79") (pinfunction "PC11_79") (pintype "bidirectional"))
    )
    (net (code "79") (name "SPI3_MOSI") (class "Default")
      (node (ref "JP4") (pin "14") (pinfunction "14_14") (pintype "passive"))
      (node (ref "U1") (pin "80") (pinfunction "PC12_80") (pintype "bidirectional"))
    )
    (net (code "80") (name "SPI3_SCK") (class "Default")
      (node (ref "JP4") (pin "18") (pinfunction "18_18") (pintype "passive"))
      (node (ref "U1") (pin "78") (pinfunction "PC10_78") (pintype "bidirectional"))
    )
    (net (code "81") (name "SWCLK") (class "Default")
      (node (ref "JP12") (pin "4") (pinfunction "4_4") (pintype "passive"))
      (node (ref "U1") (pin "76") (pinfunction "PA14_76") (pintype "bidirectional"))
    )
    (net (code "82") (name "SWDIO") (class "Default")
      (node (ref "JP12") (pin "2") (pinfunction "2_2") (pintype "passive"))
      (node (ref "U1") (pin "72") (pinfunction "PA13_72") (pintype "bidirectional"))
    )
    (net (code "83") (name "SWO") (class "Default")
      (node (ref "JP4") (pin "5") (pinfunction "5_5") (pintype "passive"))
      (node (ref "U1") (pin "89") (pinfunction "PB3_89") (pintype "bidirectional"))
    )
    (net (code "84") (name "UART1_RX") (class "Default")
      (node (ref "JP4") (pin "10") (pinfunction "10_10") (pintype "passive"))
      (node (ref "U1") (pin "93") (pinfunction "PB7_93") (pintype "bidirectional"))
    )
    (net (code "85") (name "UART1_TX") (class "Default")
      (node (ref "JP4") (pin "12") (pinfunction "12_12") (pintype "passive"))
      (node (ref "U1") (pin "92") (pinfunction "PB6_92") (pintype "bidirectional"))
    )
    (net (code "86") (name "USB_D+") (class "Default")
      (node (ref "U1") (pin "71") (pinfunction "PA12_71") (pintype "bidirectional"))
      (node (ref "U4") (pin "1") (pinfunction "D1_IN_1") (pintype "bidirectional"))
    )
    (net (code "87") (name "USB_D+_IN") (class "Default")
      (node (ref "J1") (pin "A6") (pinfunction "DP1_A6") (pintype "bidirectional"))
      (node (ref "J1") (pin "B6") (pinfunction "DP2_B6") (pintype "bidirectional"))
      (node (ref "R2") (pin "2") (pinfunction "2_2") (pintype "passive"))
    )
    (net (code "88") (name "USB_D-") (class "Default")
      (node (ref "U1") (pin "70") (pinfunction "PA11_70") (pintype "bidirectional"))
      (node (ref "U4") (pin "3") (pinfunction "D2_IN_3") (pintype "bidirectional"))
    )
    (net (code "89") (name "USB_D-_IN") (class "Default")
      (node (ref "J1") (pin "A7") (pinfunction "DN1_A7") (pintype "bidirectional"))
      (node (ref "J1") (pin "B7") (pinfunction "DN2_B7") (pintype "bidirectional"))
      (node (ref "R3") (pin "2") (pinfunction "2_2") (pintype "passive"))
    )
    (net (code "90") (name "USB_SHIELD") (class "Default")
      (node (ref "C16") (pin "1") (pinfunction "1_1") (pintype "passive"))
      (node (ref "J1") (pin "S1") (pinfunction "SHELL_GND_S1") (pintype "power_in"))
      (node (ref "J1") (pin "S2") (pinfunction "SHELL_GND_S2") (pintype "power_in"))
      (node (ref "J1") (pin "S3") (pinfunction "SHELL_GND_S3") (pintype "power_in"))
      (node (ref "J1") (pin "S4") (pinfunction "SHELL_GND_S4") (pintype "power_in"))
    )
    (net (code "91") (name "USB_VBUS") (class "Default")
      (node (ref "R14") (pin "1") (pinfunction "1_1") (pintype "passive"))
      (node (ref "U1") (pin "68") (pinfunction "PA9_68") (pintype "bidirectional"))
    )
    (net (code "92") (name "USB_VBUS_IN") (class "Default")
      (node (ref "D1") (pin "A") (pinfunction "A_A") (pintype "passive"))
      (node (ref "J1") (pin "A4_B9") (pinfunction "VBUS_A4_B9") (pintype "power_in"))
      (node (ref "J1") (pin "B4_A9") (pinfunction "VBUS_B4_A9") (pintype "power_in"))
      (node (ref "R14") (pin "2") (pinfunction "2_2") (pintype "passive"))
      (node (ref "U4") (pin "5") (pinfunction "VBUS_5") (pintype "bidirectional"))
    )
    (net (code "93") (name "VDDA") (class "Default")
      (node (ref "C13") (pin "2") (pinfunction "2_2") (pintype "passive"))
      (node (ref "L1") (pin "2") (pinfunction "2_2") (pintype "passive"))
      (node (ref "U1") (pin "21") (pinfunction "VREF+_21") (pintype "power_in"))
      (node (ref "U1") (pin "22") (pinfunction "VDDA_22") (pintype "power_in"))
    )
    (net (code "94") (name "V_EXT") (class "Default")
      (node (ref "JP8") (pin "13") (pinfunction "KL_13") (pintype "passive"))
      (node (ref "U1") (pin "33") (pinfunction "PC4_33") (pintype "bidirectional"))
    )
    (net (code "95") (name "V_INT") (class "Default")
      (node (ref "JP8") (pin "14") (pinfunction "KL_14") (pintype "passive"))
      (node (ref "U1") (pin "34") (pinfunction "PC5_34") (pintype "bidirectional"))
    )
    (net (code "96") (name "unconnected-(J1-SBU1-PadA8)") (class "Default")
      (node (ref "J1") (pin "A8") (pinfunction "SBU1_A8") (pintype "bidirectional"))
    )
    (net (code "97") (name "unconnected-(J1-SBU2-PadB8)") (class "Default")
      (node (ref "J1") (pin "B8") (pinfunction "SBU2_B8") (pintype "bidirectional"))
    )
    (net (code "98") (name "unconnected-(U1A-PA8-Pad67)") (class "Default")
      (node (ref "U1") (pin "67") (pinfunction "PA8_67") (pintype "bidirectional"))
    )
    (net (code "99") (name "unconnected-(U1A-PA10-Pad69)") (class "Default")
      (node (ref "U1") (pin "69") (pinfunction "PA10_69") (pintype "bidirectional"))
    )
    (net (code "100") (name "unconnected-(U1A-PC8-Pad65)") (class "Default")
      (node (ref "U1") (pin "65") (pinfunction "PC8_65") (pintype "bidirectional"))
    )
    (net (code "101") (name "unconnected-(U1A-PC9-Pad66)") (class "Default")
      (node (ref "U1") (pin "66") (pinfunction "PC9_66") (pintype "bidirectional"))
    )
    (net (code "102") (name "unconnected-(U1A-PD10-Pad57)") (class "Default")
      (node (ref "U1") (pin "57") (pinfunction "PD10_57") (pintype "bidirectional"))
    )
    (net (code "103") (name "unconnected-(U1A-PD11-Pad58)") (class "Default")
      (node (ref "U1") (pin "58") (pinfunction "PD11_58") (pintype "bidirectional"))
    )
    (net (code "104") (name "unconnected-(U1A-PD12-Pad59)") (class "Default")
      (node (ref "U1") (pin "59") (pinfunction "PD12_59") (pintype "bidirectional"))
    )
    (net (code "105") (name "unconnected-(U1A-PD13-Pad60)") (class "Default")
      (node (ref "U1") (pin "60") (pinfunction "PD13_60") (pintype "bidirectional"))
    )
    (net (code "106") (name "unconnected-(U1A-PD14-Pad61)") (class "Default")
      (node (ref "U1") (pin "61") (pinfunction "PD14_61") (pintype "bidirectional"))
    )
    (net (code "107") (name "unconnected-(U1B-PE15-Pad46)") (class "Default")
      (node (ref "U1") (pin "46") (pinfunction "PE15_46") (pintype "bidirectional"))
    )
  )
)
